# fpga_sram.net
KiCad netlist of a schematic drawn in Altium Designer
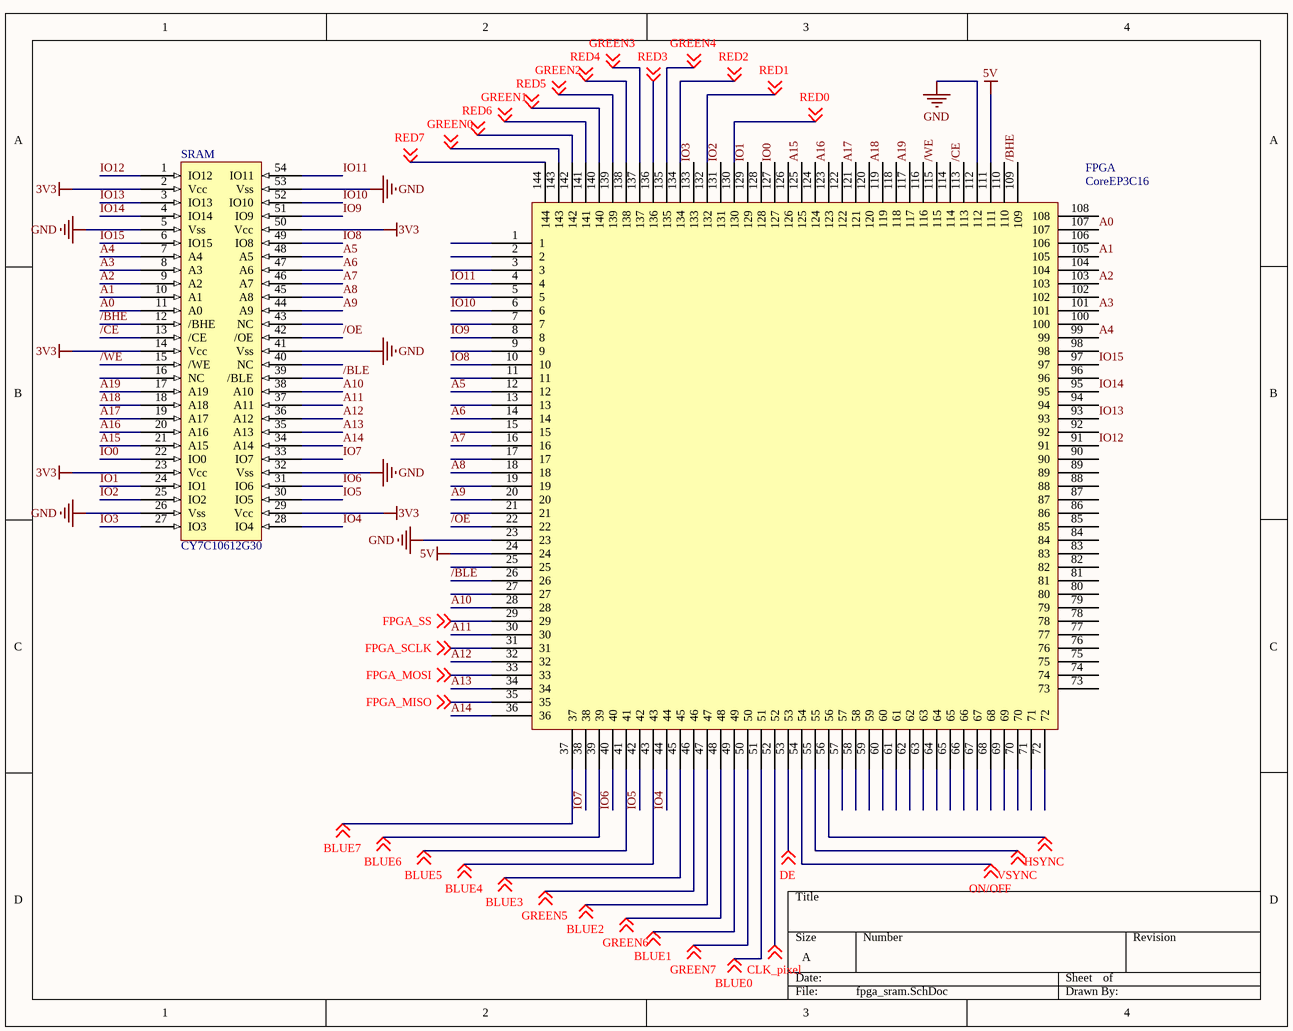
[diagram p0: fpga_sram.SchDoc]

(export (version "E")
  (design (tool "Eeschema 10.0.6"))
  (components
    (comp (ref "FPGA")
      (value "CoreEP3C16")
      (footprint "CoreEP3C16")
      (libsource (lib "CoreEP3C16") (part "CoreEP3C16"))
    )
    (comp (ref "SRAM")
      (value "CY7C10612G30")
      (footprint "TSOP54")
      (libsource (lib "CY7C10612G30") (part "CY7C10612G30"))
    )
  )
  (nets
    (net (code "1") (name "/A0") (class "Default")
      (node (ref "FPGA") (pin "107") (pinfunction "107_107") (pintype "passive"))
      (node (ref "SRAM") (pin "11") (pinfunction "A0_11") (pintype "input"))
    )
    (net (code "2") (name "/A1") (class "Default")
      (node (ref "FPGA") (pin "105") (pinfunction "105_105") (pintype "passive"))
      (node (ref "SRAM") (pin "10") (pinfunction "A1_10") (pintype "input"))
    )
    (net (code "3") (name "/A2") (class "Default")
      (node (ref "FPGA") (pin "103") (pinfunction "103_103") (pintype "passive"))
      (node (ref "SRAM") (pin "9") (pinfunction "A2_9") (pintype "input"))
    )
    (net (code "4") (name "/A3") (class "Default")
      (node (ref "FPGA") (pin "101") (pinfunction "101_101") (pintype "passive"))
      (node (ref "SRAM") (pin "8") (pinfunction "A3_8") (pintype "input"))
    )
    (net (code "5") (name "/A4") (class "Default")
      (node (ref "FPGA") (pin "99") (pinfunction "99_99") (pintype "passive"))
      (node (ref "SRAM") (pin "7") (pinfunction "A4_7") (pintype "input"))
    )
    (net (code "6") (name "/A5") (class "Default")
      (node (ref "FPGA") (pin "12") (pinfunction "12_12") (pintype "passive"))
      (node (ref "SRAM") (pin "48") (pinfunction "A5_48") (pintype "input"))
    )
    (net (code "7") (name "/A6") (class "Default")
      (node (ref "FPGA") (pin "14") (pinfunction "14_14") (pintype "passive"))
      (node (ref "SRAM") (pin "47") (pinfunction "A6_47") (pintype "input"))
    )
    (net (code "8") (name "/A7") (class "Default")
      (node (ref "FPGA") (pin "16") (pinfunction "16_16") (pintype "passive"))
      (node (ref "SRAM") (pin "46") (pinfunction "A7_46") (pintype "input"))
    )
    (net (code "9") (name "/A8") (class "Default")
      (node (ref "FPGA") (pin "18") (pinfunction "18_18") (pintype "passive"))
      (node (ref "SRAM") (pin "45") (pinfunction "A8_45") (pintype "input"))
    )
    (net (code "10") (name "/A9") (class "Default")
      (node (ref "FPGA") (pin "20") (pinfunction "20_20") (pintype "passive"))
      (node (ref "SRAM") (pin "44") (pinfunction "A9_44") (pintype "input"))
    )
    (net (code "11") (name "/A10") (class "Default")
      (node (ref "FPGA") (pin "28") (pinfunction "28_28") (pintype "passive"))
      (node (ref "SRAM") (pin "38") (pinfunction "A10_38") (pintype "input"))
    )
    (net (code "12") (name "/A11") (class "Default")
      (node (ref "FPGA") (pin "30") (pinfunction "30_30") (pintype "passive"))
      (node (ref "SRAM") (pin "37") (pinfunction "A11_37") (pintype "input"))
    )
    (net (code "13") (name "/A12") (class "Default")
      (node (ref "FPGA") (pin "32") (pinfunction "32_32") (pintype "passive"))
      (node (ref "SRAM") (pin "36") (pinfunction "A12_36") (pintype "input"))
    )
    (net (code "14") (name "/A13") (class "Default")
      (node (ref "FPGA") (pin "34") (pinfunction "34_34") (pintype "passive"))
      (node (ref "SRAM") (pin "35") (pinfunction "A13_35") (pintype "input"))
    )
    (net (code "15") (name "/A14") (class "Default")
      (node (ref "FPGA") (pin "36") (pinfunction "36_36") (pintype "passive"))
      (node (ref "SRAM") (pin "34") (pinfunction "A14_34") (pintype "input"))
    )
    (net (code "16") (name "/A15") (class "Default")
      (node (ref "FPGA") (pin "125") (pinfunction "125_125") (pintype "passive"))
      (node (ref "SRAM") (pin "21") (pinfunction "A15_21") (pintype "input"))
    )
    (net (code "17") (name "/A16") (class "Default")
      (node (ref "FPGA") (pin "123") (pinfunction "123_123") (pintype "passive"))
      (node (ref "SRAM") (pin "20") (pinfunction "A16_20") (pintype "input"))
    )
    (net (code "18") (name "/A17") (class "Default")
      (node (ref "FPGA") (pin "121") (pinfunction "121_121") (pintype "passive"))
      (node (ref "SRAM") (pin "19") (pinfunction "A17_19") (pintype "input"))
    )
    (net (code "19") (name "/A18") (class "Default")
      (node (ref "FPGA") (pin "119") (pinfunction "119_119") (pintype "passive"))
      (node (ref "SRAM") (pin "18") (pinfunction "A18_18") (pintype "input"))
    )
    (net (code "20") (name "/A19") (class "Default")
      (node (ref "FPGA") (pin "117") (pinfunction "117_117") (pintype "passive"))
      (node (ref "SRAM") (pin "17") (pinfunction "A19_17") (pintype "input"))
    )
    (net (code "21") (name "/IO0") (class "Default")
      (node (ref "FPGA") (pin "127") (pinfunction "127_127") (pintype "passive"))
      (node (ref "SRAM") (pin "22") (pinfunction "IO0_22") (pintype "input"))
    )
    (net (code "22") (name "/IO1") (class "Default")
      (node (ref "FPGA") (pin "129") (pinfunction "129_129") (pintype "passive"))
      (node (ref "SRAM") (pin "24") (pinfunction "IO1_24") (pintype "input"))
    )
    (net (code "23") (name "/IO2") (class "Default")
      (node (ref "FPGA") (pin "131") (pinfunction "131_131") (pintype "passive"))
      (node (ref "SRAM") (pin "25") (pinfunction "IO2_25") (pintype "input"))
    )
    (net (code "24") (name "/IO3") (class "Default")
      (node (ref "FPGA") (pin "133") (pinfunction "133_133") (pintype "passive"))
      (node (ref "SRAM") (pin "27") (pinfunction "IO3_27") (pintype "input"))
    )
    (net (code "25") (name "/IO4") (class "Default")
      (node (ref "FPGA") (pin "44") (pinfunction "44_44") (pintype "passive"))
      (node (ref "SRAM") (pin "28") (pinfunction "IO4_28") (pintype "input"))
    )
    (net (code "26") (name "/IO5") (class "Default")
      (node (ref "FPGA") (pin "42") (pinfunction "42_42") (pintype "passive"))
      (node (ref "SRAM") (pin "30") (pinfunction "IO5_30") (pintype "input"))
    )
    (net (code "27") (name "/IO6") (class "Default")
      (node (ref "FPGA") (pin "40") (pinfunction "40_40") (pintype "passive"))
      (node (ref "SRAM") (pin "31") (pinfunction "IO6_31") (pintype "input"))
    )
    (net (code "28") (name "/IO7") (class "Default")
      (node (ref "FPGA") (pin "38") (pinfunction "38_38") (pintype "passive"))
      (node (ref "SRAM") (pin "33") (pinfunction "IO7_33") (pintype "input"))
    )
    (net (code "29") (name "/IO8") (class "Default")
      (node (ref "FPGA") (pin "10") (pinfunction "10_10") (pintype "passive"))
      (node (ref "SRAM") (pin "49") (pinfunction "IO8_49") (pintype "input"))
    )
    (net (code "30") (name "/IO9") (class "Default")
      (node (ref "FPGA") (pin "8") (pinfunction "8_8") (pintype "passive"))
      (node (ref "SRAM") (pin "51") (pinfunction "IO9_51") (pintype "input"))
    )
    (net (code "31") (name "/IO10") (class "Default")
      (node (ref "FPGA") (pin "6") (pinfunction "6_6") (pintype "passive"))
      (node (ref "SRAM") (pin "52") (pinfunction "IO10_52") (pintype "input"))
    )
    (net (code "32") (name "/IO11") (class "Default")
      (node (ref "FPGA") (pin "4") (pinfunction "4_4") (pintype "passive"))
      (node (ref "SRAM") (pin "54") (pinfunction "IO11_54") (pintype "input"))
    )
    (net (code "33") (name "/IO12") (class "Default")
      (node (ref "FPGA") (pin "91") (pinfunction "91_91") (pintype "passive"))
      (node (ref "SRAM") (pin "1") (pinfunction "IO12_1") (pintype "input"))
    )
    (net (code "34") (name "/IO13") (class "Default")
      (node (ref "FPGA") (pin "93") (pinfunction "93_93") (pintype "passive"))
      (node (ref "SRAM") (pin "3") (pinfunction "IO13_3") (pintype "input"))
    )
    (net (code "35") (name "/IO14") (class "Default")
      (node (ref "FPGA") (pin "95") (pinfunction "95_95") (pintype "passive"))
      (node (ref "SRAM") (pin "4") (pinfunction "IO14_4") (pintype "input"))
    )
    (net (code "36") (name "/IO15") (class "Default")
      (node (ref "FPGA") (pin "97") (pinfunction "97_97") (pintype "passive"))
      (node (ref "SRAM") (pin "6") (pinfunction "IO15_6") (pintype "input"))
    )
    (net (code "37") (name "/{slash}BHE") (class "Default")
      (node (ref "FPGA") (pin "109") (pinfunction "109_109") (pintype "passive"))
      (node (ref "SRAM") (pin "12") (pinfunction "/BHE_12") (pintype "input"))
    )
    (net (code "38") (name "/{slash}BLE") (class "Default")
      (node (ref "FPGA") (pin "26") (pinfunction "26_26") (pintype "passive"))
      (node (ref "SRAM") (pin "39") (pinfunction "/BLE_39") (pintype "input"))
    )
    (net (code "39") (name "/{slash}CE") (class "Default")
      (node (ref "FPGA") (pin "113") (pinfunction "113_113") (pintype "passive"))
      (node (ref "SRAM") (pin "13") (pinfunction "/CE_13") (pintype "input"))
    )
    (net (code "40") (name "/{slash}OE") (class "Default")
      (node (ref "FPGA") (pin "22") (pinfunction "22_22") (pintype "passive"))
      (node (ref "SRAM") (pin "42") (pinfunction "/OE_42") (pintype "input"))
    )
    (net (code "41") (name "/{slash}WE") (class "Default")
      (node (ref "FPGA") (pin "115") (pinfunction "115_115") (pintype "passive"))
      (node (ref "SRAM") (pin "15") (pinfunction "/WE_15") (pintype "input"))
    )
    (net (code "42") (name "3V3") (class "Default")
      (node (ref "SRAM") (pin "14") (pinfunction "Vcc_14") (pintype "input"))
      (node (ref "SRAM") (pin "2") (pinfunction "Vcc_2") (pintype "input"))
      (node (ref "SRAM") (pin "23") (pinfunction "Vcc_23") (pintype "input"))
      (node (ref "SRAM") (pin "29") (pinfunction "Vcc_29") (pintype "input"))
      (node (ref "SRAM") (pin "50") (pinfunction "Vcc_50") (pintype "input"))
    )
    (net (code "43") (name "5V") (class "Default")
      (node (ref "FPGA") (pin "111") (pinfunction "111_111") (pintype "passive"))
      (node (ref "FPGA") (pin "24") (pinfunction "24_24") (pintype "passive"))
    )
    (net (code "44") (name "BLUE0") (class "Default")
      (node (ref "FPGA") (pin "51") (pinfunction "51_51") (pintype "passive"))
    )
    (net (code "45") (name "BLUE1") (class "Default")
      (node (ref "FPGA") (pin "49") (pinfunction "49_49") (pintype "passive"))
    )
    (net (code "46") (name "BLUE2") (class "Default")
      (node (ref "FPGA") (pin "47") (pinfunction "47_47") (pintype "passive"))
    )
    (net (code "47") (name "BLUE3") (class "Default")
      (node (ref "FPGA") (pin "45") (pinfunction "45_45") (pintype "passive"))
    )
    (net (code "48") (name "BLUE4") (class "Default")
      (node (ref "FPGA") (pin "43") (pinfunction "43_43") (pintype "passive"))
    )
    (net (code "49") (name "BLUE5") (class "Default")
      (node (ref "FPGA") (pin "41") (pinfunction "41_41") (pintype "passive"))
    )
    (net (code "50") (name "BLUE6") (class "Default")
      (node (ref "FPGA") (pin "39") (pinfunction "39_39") (pintype "passive"))
    )
    (net (code "51") (name "BLUE7") (class "Default")
      (node (ref "FPGA") (pin "37") (pinfunction "37_37") (pintype "passive"))
    )
    (net (code "52") (name "CLK_pixel") (class "Default")
      (node (ref "FPGA") (pin "52") (pinfunction "52_52") (pintype "passive"))
    )
    (net (code "53") (name "DE") (class "Default")
      (node (ref "FPGA") (pin "53") (pinfunction "53_53") (pintype "passive"))
    )
    (net (code "54") (name "FPGA_MISO") (class "Default")
      (node (ref "FPGA") (pin "35") (pinfunction "35_35") (pintype "passive"))
    )
    (net (code "55") (name "FPGA_MOSI") (class "Default")
      (node (ref "FPGA") (pin "33") (pinfunction "33_33") (pintype "passive"))
    )
    (net (code "56") (name "FPGA_SCLK") (class "Default")
      (node (ref "FPGA") (pin "31") (pinfunction "31_31") (pintype "passive"))
    )
    (net (code "57") (name "FPGA_SS") (class "Default")
      (node (ref "FPGA") (pin "29") (pinfunction "29_29") (pintype "passive"))
    )
    (net (code "58") (name "GND") (class "Default")
      (node (ref "FPGA") (pin "112") (pinfunction "112_112") (pintype "passive"))
      (node (ref "FPGA") (pin "23") (pinfunction "23_23") (pintype "passive"))
      (node (ref "SRAM") (pin "26") (pinfunction "Vss_26") (pintype "input"))
      (node (ref "SRAM") (pin "32") (pinfunction "Vss_32") (pintype "input"))
      (node (ref "SRAM") (pin "41") (pinfunction "Vss_41") (pintype "input"))
      (node (ref "SRAM") (pin "5") (pinfunction "Vss_5") (pintype "input"))
      (node (ref "SRAM") (pin "53") (pinfunction "Vss_53") (pintype "input"))
    )
    (net (code "59") (name "GREEN0") (class "Default")
      (node (ref "FPGA") (pin "143") (pinfunction "143_143") (pintype "passive"))
    )
    (net (code "60") (name "GREEN1") (class "Default")
      (node (ref "FPGA") (pin "141") (pinfunction "141_141") (pintype "passive"))
    )
    (net (code "61") (name "GREEN2") (class "Default")
      (node (ref "FPGA") (pin "139") (pinfunction "139_139") (pintype "passive"))
    )
    (net (code "62") (name "GREEN3") (class "Default")
      (node (ref "FPGA") (pin "137") (pinfunction "137_137") (pintype "passive"))
    )
    (net (code "63") (name "GREEN4") (class "Default")
      (node (ref "FPGA") (pin "135") (pinfunction "135_135") (pintype "passive"))
    )
    (net (code "64") (name "GREEN5") (class "Default")
      (node (ref "FPGA") (pin "46") (pinfunction "46_46") (pintype "passive"))
    )
    (net (code "65") (name "GREEN6") (class "Default")
      (node (ref "FPGA") (pin "48") (pinfunction "48_48") (pintype "passive"))
    )
    (net (code "66") (name "GREEN7") (class "Default")
      (node (ref "FPGA") (pin "50") (pinfunction "50_50") (pintype "passive"))
    )
    (net (code "67") (name "HSYNC") (class "Default")
      (node (ref "FPGA") (pin "56") (pinfunction "56_56") (pintype "passive"))
    )
    (net (code "68") (name "ON{slash}OFF") (class "Default")
      (node (ref "FPGA") (pin "54") (pinfunction "54_54") (pintype "passive"))
    )
    (net (code "69") (name "RED0") (class "Default")
      (node (ref "FPGA") (pin "130") (pinfunction "130_130") (pintype "passive"))
    )
    (net (code "70") (name "RED1") (class "Default")
      (node (ref "FPGA") (pin "132") (pinfunction "132_132") (pintype "passive"))
    )
    (net (code "71") (name "RED2") (class "Default")
      (node (ref "FPGA") (pin "134") (pinfunction "134_134") (pintype "passive"))
    )
    (net (code "72") (name "RED3") (class "Default")
      (node (ref "FPGA") (pin "136") (pinfunction "136_136") (pintype "passive"))
    )
    (net (code "73") (name "RED4") (class "Default")
      (node (ref "FPGA") (pin "138") (pinfunction "138_138") (pintype "passive"))
    )
    (net (code "74") (name "RED5") (class "Default")
      (node (ref "FPGA") (pin "140") (pinfunction "140_140") (pintype "passive"))
    )
    (net (code "75") (name "RED6") (class "Default")
      (node (ref "FPGA") (pin "142") (pinfunction "142_142") (pintype "passive"))
    )
    (net (code "76") (name "RED7") (class "Default")
      (node (ref "FPGA") (pin "144") (pinfunction "144_144") (pintype "passive"))
    )
    (net (code "77") (name "VSYNC") (class "Default")
      (node (ref "FPGA") (pin "55") (pinfunction "55_55") (pintype "passive"))
    )
    (net (code "78") (name "unconnected-(FPGA-Pad1)") (class "Default")
      (node (ref "FPGA") (pin "1") (pinfunction "1_1") (pintype "passive"))
    )
    (net (code "79") (name "unconnected-(FPGA-Pad2)") (class "Default")
      (node (ref "FPGA") (pin "2") (pinfunction "2_2") (pintype "passive"))
    )
    (net (code "80") (name "unconnected-(FPGA-Pad3)") (class "Default")
      (node (ref "FPGA") (pin "3") (pinfunction "3_3") (pintype "passive"))
    )
    (net (code "81") (name "unconnected-(FPGA-Pad5)") (class "Default")
      (node (ref "FPGA") (pin "5") (pinfunction "5_5") (pintype "passive"))
    )
    (net (code "82") (name "unconnected-(FPGA-Pad7)") (class "Default")
      (node (ref "FPGA") (pin "7") (pinfunction "7_7") (pintype "passive"))
    )
    (net (code "83") (name "unconnected-(FPGA-Pad9)") (class "Default")
      (node (ref "FPGA") (pin "9") (pinfunction "9_9") (pintype "passive"))
    )
    (net (code "84") (name "unconnected-(FPGA-Pad11)") (class "Default")
      (node (ref "FPGA") (pin "11") (pinfunction "11_11") (pintype "passive"))
    )
    (net (code "85") (name "unconnected-(FPGA-Pad13)") (class "Default")
      (node (ref "FPGA") (pin "13") (pinfunction "13_13") (pintype "passive"))
    )
    (net (code "86") (name "unconnected-(FPGA-Pad15)") (class "Default")
      (node (ref "FPGA") (pin "15") (pinfunction "15_15") (pintype "passive"))
    )
    (net (code "87") (name "unconnected-(FPGA-Pad17)") (class "Default")
      (node (ref "FPGA") (pin "17") (pinfunction "17_17") (pintype "passive"))
    )
    (net (code "88") (name "unconnected-(FPGA-Pad19)") (class "Default")
      (node (ref "FPGA") (pin "19") (pinfunction "19_19") (pintype "passive"))
    )
    (net (code "89") (name "unconnected-(FPGA-Pad21)") (class "Default")
      (node (ref "FPGA") (pin "21") (pinfunction "21_21") (pintype "passive"))
    )
    (net (code "90") (name "unconnected-(FPGA-Pad25)") (class "Default")
      (node (ref "FPGA") (pin "25") (pinfunction "25_25") (pintype "passive"))
    )
    (net (code "91") (name "unconnected-(FPGA-Pad27)") (class "Default")
      (node (ref "FPGA") (pin "27") (pinfunction "27_27") (pintype "passive"))
    )
    (net (code "92") (name "unconnected-(FPGA-Pad57)") (class "Default")
      (node (ref "FPGA") (pin "57") (pinfunction "57_57") (pintype "passive"))
    )
    (net (code "93") (name "unconnected-(FPGA-Pad58)") (class "Default")
      (node (ref "FPGA") (pin "58") (pinfunction "58_58") (pintype "passive"))
    )
    (net (code "94") (name "unconnected-(FPGA-Pad59)") (class "Default")
      (node (ref "FPGA") (pin "59") (pinfunction "59_59") (pintype "passive"))
    )
    (net (code "95") (name "unconnected-(FPGA-Pad60)") (class "Default")
      (node (ref "FPGA") (pin "60") (pinfunction "60_60") (pintype "passive"))
    )
    (net (code "96") (name "unconnected-(FPGA-Pad61)") (class "Default")
      (node (ref "FPGA") (pin "61") (pinfunction "61_61") (pintype "passive"))
    )
    (net (code "97") (name "unconnected-(FPGA-Pad62)") (class "Default")
      (node (ref "FPGA") (pin "62") (pinfunction "62_62") (pintype "passive"))
    )
    (net (code "98") (name "unconnected-(FPGA-Pad63)") (class "Default")
      (node (ref "FPGA") (pin "63") (pinfunction "63_63") (pintype "passive"))
    )
    (net (code "99") (name "unconnected-(FPGA-Pad64)") (class "Default")
      (node (ref "FPGA") (pin "64") (pinfunction "64_64") (pintype "passive"))
    )
    (net (code "100") (name "unconnected-(FPGA-Pad65)") (class "Default")
      (node (ref "FPGA") (pin "65") (pinfunction "65_65") (pintype "passive"))
    )
    (net (code "101") (name "unconnected-(FPGA-Pad66)") (class "Default")
      (node (ref "FPGA") (pin "66") (pinfunction "66_66") (pintype "passive"))
    )
    (net (code "102") (name "unconnected-(FPGA-Pad67)") (class "Default")
      (node (ref "FPGA") (pin "67") (pinfunction "67_67") (pintype "passive"))
    )
    (net (code "103") (name "unconnected-(FPGA-Pad68)") (class "Default")
      (node (ref "FPGA") (pin "68") (pinfunction "68_68") (pintype "passive"))
    )
    (net (code "104") (name "unconnected-(FPGA-Pad69)") (class "Default")
      (node (ref "FPGA") (pin "69") (pinfunction "69_69") (pintype "passive"))
    )
    (net (code "105") (name "unconnected-(FPGA-Pad70)") (class "Default")
      (node (ref "FPGA") (pin "70") (pinfunction "70_70") (pintype "passive"))
    )
    (net (code "106") (name "unconnected-(FPGA-Pad71)") (class "Default")
      (node (ref "FPGA") (pin "71") (pinfunction "71_71") (pintype "passive"))
    )
    (net (code "107") (name "unconnected-(FPGA-Pad72)") (class "Default")
      (node (ref "FPGA") (pin "72") (pinfunction "72_72") (pintype "passive"))
    )
    (net (code "108") (name "unconnected-(FPGA-Pad73)") (class "Default")
      (node (ref "FPGA") (pin "73") (pinfunction "73_73") (pintype "passive"))
    )
    (net (code "109") (name "unconnected-(FPGA-Pad74)") (class "Default")
      (node (ref "FPGA") (pin "74") (pinfunction "74_74") (pintype "passive"))
    )
    (net (code "110") (name "unconnected-(FPGA-Pad75)") (class "Default")
      (node (ref "FPGA") (pin "75") (pinfunction "75_75") (pintype "passive"))
    )
    (net (code "111") (name "unconnected-(FPGA-Pad76)") (class "Default")
      (node (ref "FPGA") (pin "76") (pinfunction "76_76") (pintype "passive"))
    )
    (net (code "112") (name "unconnected-(FPGA-Pad77)") (class "Default")
      (node (ref "FPGA") (pin "77") (pinfunction "77_77") (pintype "passive"))
    )
    (net (code "113") (name "unconnected-(FPGA-Pad78)") (class "Default")
      (node (ref "FPGA") (pin "78") (pinfunction "78_78") (pintype "passive"))
    )
    (net (code "114") (name "unconnected-(FPGA-Pad79)") (class "Default")
      (node (ref "FPGA") (pin "79") (pinfunction "79_79") (pintype "passive"))
    )
    (net (code "115") (name "unconnected-(FPGA-Pad80)") (class "Default")
      (node (ref "FPGA") (pin "80") (pinfunction "80_80") (pintype "passive"))
    )
    (net (code "116") (name "unconnected-(FPGA-Pad81)") (class "Default")
      (node (ref "FPGA") (pin "81") (pinfunction "81_81") (pintype "passive"))
    )
    (net (code "117") (name "unconnected-(FPGA-Pad82)") (class "Default")
      (node (ref "FPGA") (pin "82") (pinfunction "82_82") (pintype "passive"))
    )
    (net (code "118") (name "unconnected-(FPGA-Pad83)") (class "Default")
      (node (ref "FPGA") (pin "83") (pinfunction "83_83") (pintype "passive"))
    )
    (net (code "119") (name "unconnected-(FPGA-Pad84)") (class "Default")
      (node (ref "FPGA") (pin "84") (pinfunction "84_84") (pintype "passive"))
    )
    (net (code "120") (name "unconnected-(FPGA-Pad85)") (class "Default")
      (node (ref "FPGA") (pin "85") (pinfunction "85_85") (pintype "passive"))
    )
    (net (code "121") (name "unconnected-(FPGA-Pad86)") (class "Default")
      (node (ref "FPGA") (pin "86") (pinfunction "86_86") (pintype "passive"))
    )
    (net (code "122") (name "unconnected-(FPGA-Pad87)") (class "Default")
      (node (ref "FPGA") (pin "87") (pinfunction "87_87") (pintype "passive"))
    )
    (net (code "123") (name "unconnected-(FPGA-Pad88)") (class "Default")
      (node (ref "FPGA") (pin "88") (pinfunction "88_88") (pintype "passive"))
    )
    (net (code "124") (name "unconnected-(FPGA-Pad89)") (class "Default")
      (node (ref "FPGA") (pin "89") (pinfunction "89_89") (pintype "passive"))
    )
    (net (code "125") (name "unconnected-(FPGA-Pad90)") (class "Default")
      (node (ref "FPGA") (pin "90") (pinfunction "90_90") (pintype "passive"))
    )
    (net (code "126") (name "unconnected-(FPGA-Pad92)") (class "Default")
      (node (ref "FPGA") (pin "92") (pinfunction "92_92") (pintype "passive"))
    )
    (net (code "127") (name "unconnected-(FPGA-Pad94)") (class "Default")
      (node (ref "FPGA") (pin "94") (pinfunction "94_94") (pintype "passive"))
    )
    (net (code "128") (name "unconnected-(FPGA-Pad96)") (class "Default")
      (node (ref "FPGA") (pin "96") (pinfunction "96_96") (pintype "passive"))
    )
    (net (code "129") (name "unconnected-(FPGA-Pad98)") (class "Default")
      (node (ref "FPGA") (pin "98") (pinfunction "98_98") (pintype "passive"))
    )
    (net (code "130") (name "unconnected-(FPGA-Pad100)") (class "Default")
      (node (ref "FPGA") (pin "100") (pinfunction "100_100") (pintype "passive"))
    )
    (net (code "131") (name "unconnected-(FPGA-Pad102)") (class "Default")
      (node (ref "FPGA") (pin "102") (pinfunction "102_102") (pintype "passive"))
    )
    (net (code "132") (name "unconnected-(FPGA-Pad104)") (class "Default")
      (node (ref "FPGA") (pin "104") (pinfunction "104_104") (pintype "passive"))
    )
    (net (code "133") (name "unconnected-(FPGA-Pad106)") (class "Default")
      (node (ref "FPGA") (pin "106") (pinfunction "106_106") (pintype "passive"))
    )
    (net (code "134") (name "unconnected-(FPGA-Pad108)") (class "Default")
      (node (ref "FPGA") (pin "108") (pinfunction "108_108") (pintype "passive"))
    )
    (net (code "135") (name "unconnected-(FPGA-Pad110)") (class "Default")
      (node (ref "FPGA") (pin "110") (pinfunction "110_110") (pintype "passive"))
    )
    (net (code "136") (name "unconnected-(FPGA-Pad114)") (class "Default")
      (node (ref "FPGA") (pin "114") (pinfunction "114_114") (pintype "passive"))
    )
    (net (code "137") (name "unconnected-(FPGA-Pad116)") (class "Default")
      (node (ref "FPGA") (pin "116") (pinfunction "116_116") (pintype "passive"))
    )
    (net (code "138") (name "unconnected-(FPGA-Pad118)") (class "Default")
      (node (ref "FPGA") (pin "118") (pinfunction "118_118") (pintype "passive"))
    )
    (net (code "139") (name "unconnected-(FPGA-Pad120)") (class "Default")
      (node (ref "FPGA") (pin "120") (pinfunction "120_120") (pintype "passive"))
    )
    (net (code "140") (name "unconnected-(FPGA-Pad122)") (class "Default")
      (node (ref "FPGA") (pin "122") (pinfunction "122_122") (pintype "passive"))
    )
    (net (code "141") (name "unconnected-(FPGA-Pad124)") (class "Default")
      (node (ref "FPGA") (pin "124") (pinfunction "124_124") (pintype "passive"))
    )
    (net (code "142") (name "unconnected-(FPGA-Pad126)") (class "Default")
      (node (ref "FPGA") (pin "126") (pinfunction "126_126") (pintype "passive"))
    )
    (net (code "143") (name "unconnected-(FPGA-Pad128)") (class "Default")
      (node (ref "FPGA") (pin "128") (pinfunction "128_128") (pintype "passive"))
    )
    (net (code "144") (name "unconnected-(SRAM-NC-Pad16)") (class "Default")
      (node (ref "SRAM") (pin "16") (pinfunction "NC_16") (pintype "input"))
    )
    (net (code "145") (name "unconnected-(SRAM-NC-Pad40)") (class "Default")
      (node (ref "SRAM") (pin "40") (pinfunction "NC_40") (pintype "input"))
    )
    (net (code "146") (name "unconnected-(SRAM-NC-Pad43)") (class "Default")
      (node (ref "SRAM") (pin "43") (pinfunction "NC_43") (pintype "input"))
    )
  )
)
